# Top.net
KiCad netlist of a schematic drawn in Altium Designer
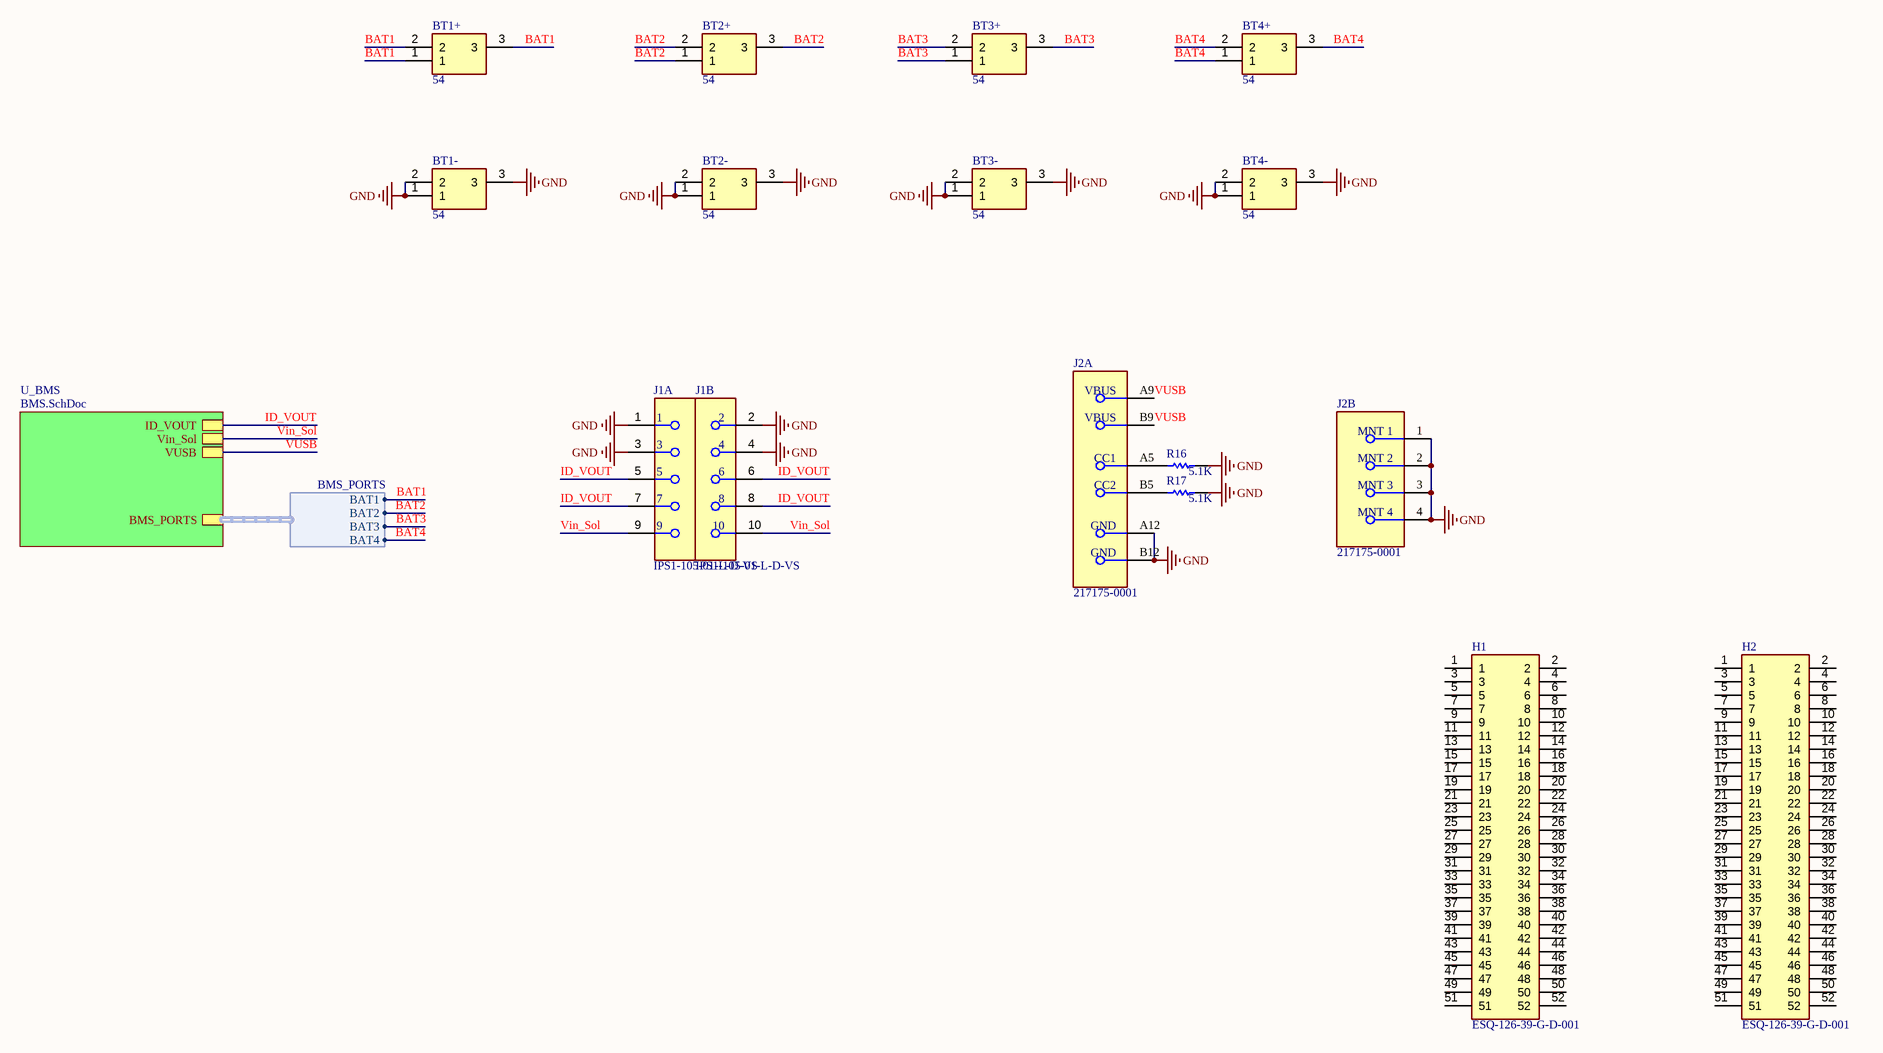
[diagram p0: Top.SchDoc]

(export (version "E")
  (design (tool "Eeschema 10.0.6"))
  (components
    (comp (ref "BT1+")
      (value "54")
      (footprint "54")
      (description "Battery")
      (fields (field (name "MOUSER PART NUMBER") "534-54"))
      (libsource (lib "Hitesh Bhoyar") (part "54"))
    )
    (comp (ref "BT1-")
      (value "54")
      (footprint "54")
      (description "Battery")
      (fields (field (name "MOUSER PART NUMBER") "534-54"))
      (libsource (lib "Hitesh Bhoyar") (part "54"))
    )
    (comp (ref "BT2+")
      (value "54")
      (footprint "54")
      (description "Battery")
      (fields (field (name "MOUSER PART NUMBER") "534-54"))
      (libsource (lib "Hitesh Bhoyar") (part "54"))
    )
    (comp (ref "BT2-")
      (value "54")
      (footprint "54")
      (description "Battery")
      (fields (field (name "MOUSER PART NUMBER") "534-54"))
      (libsource (lib "Hitesh Bhoyar") (part "54"))
    )
    (comp (ref "BT3+")
      (value "54")
      (footprint "54")
      (description "Battery")
      (fields (field (name "MOUSER PART NUMBER") "534-54"))
      (libsource (lib "Hitesh Bhoyar") (part "54"))
    )
    (comp (ref "BT3-")
      (value "54")
      (footprint "54")
      (description "Battery")
      (fields (field (name "MOUSER PART NUMBER") "534-54"))
      (libsource (lib "Hitesh Bhoyar") (part "54"))
    )
    (comp (ref "BT4+")
      (value "54")
      (footprint "54")
      (description "Battery")
      (fields (field (name "MOUSER PART NUMBER") "534-54"))
      (libsource (lib "Hitesh Bhoyar") (part "54"))
    )
    (comp (ref "BT4-")
      (value "54")
      (footprint "54")
      (description "Battery")
      (fields (field (name "MOUSER PART NUMBER") "534-54"))
      (libsource (lib "Hitesh Bhoyar") (part "54"))
    )
    (comp (ref "H1")
      (value "ESQ-126-39-G-D-001")
      (footprint "RHDR52W64P254_2X26_6654X495X1135P")
      (description "PC / 104 Connectors Elevated Socket Strip")
      (fields (field (name "MOUSER PART NUMBER") "200-ESQ12639GD001"))
      (libsource (lib "Hitesh Bhoyar") (part "ESQ-126-39-G-D-001"))
    )
    (comp (ref "H2")
      (value "ESQ-126-39-G-D-001")
      (footprint "RHDR52W64P254_2X26_6654X495X1135P")
      (description "PC / 104 Connectors Elevated Socket Strip")
      (fields (field (name "MOUSER PART NUMBER") "200-ESQ12639GD001"))
      (libsource (lib "Hitesh Bhoyar") (part "ESQ-126-39-G-D-001"))
    )
    (comp (ref "J1")
      (value "IPS1-105-01-L-D-VS")
      (footprint "FP-IPS1-105-01-L-D-VS-MFG")
      (description "CONN RCPT 10POS 0.1 GOLD SMD")
      (fields
        (field (name "MANUFACTURER") "Samtec")
        (field (name "OCTOPART") "https://octopart.com/ips1-105-01-l-d-vs-samtec-19544880")
      )
      (libsource (lib "Altium Content Vault") (part "393b6539e713c610e9ddbd64c51154e"))
    )
    (comp (ref "J2")
      (value "217175-0001")
      (footprint "FP-217175-0001-MFG")
      (description "CONN RCP USB2.0 C 6+18P SMD RA")
      (libsource (lib "Altium Content Vault") (part "6a66c69350f09309f94811689c98437"))
    )
    (comp (ref "R16")
      (value "5.1K")
      (footprint "RESC1608X55X30LL15T15")
      (fields (field (name "PART NUMBER") "ERJ-3GEYJ512V") (field (name "MANUFACTURER") "Panasonic"))
      (libsource (lib "Altium Content Vault") (part "RES"))
    )
    (comp (ref "R17")
      (value "5.1K")
      (footprint "RESC1608X55X30LL15T15")
      (fields (field (name "PART NUMBER") "ERJ-3GEYJ512V") (field (name "MANUFACTURER") "Panasonic"))
      (libsource (lib "Altium Content Vault") (part "RES"))
    )
  )
  (nets
    (net (code "2") (name "/BAT1") (class "Default")
      (node (ref "BT1+") (pin "1") (pinfunction "1_1") (pintype "passive"))
      (node (ref "BT1+") (pin "2") (pinfunction "2_2") (pintype "passive"))
      (node (ref "BT1+") (pin "3") (pinfunction "3_3") (pintype "passive"))
    )
    (net (code "3") (name "/BAT2") (class "Default")
      (node (ref "BT2+") (pin "1") (pinfunction "1_1") (pintype "passive"))
      (node (ref "BT2+") (pin "2") (pinfunction "2_2") (pintype "passive"))
      (node (ref "BT2+") (pin "3") (pinfunction "3_3") (pintype "passive"))
    )
    (net (code "4") (name "/BAT3") (class "Default")
      (node (ref "BT3+") (pin "1") (pinfunction "1_1") (pintype "passive"))
      (node (ref "BT3+") (pin "2") (pinfunction "2_2") (pintype "passive"))
      (node (ref "BT3+") (pin "3") (pinfunction "3_3") (pintype "passive"))
    )
    (net (code "5") (name "/BAT4") (class "Default")
      (node (ref "BT4+") (pin "1") (pinfunction "1_1") (pintype "passive"))
      (node (ref "BT4+") (pin "2") (pinfunction "2_2") (pintype "passive"))
      (node (ref "BT4+") (pin "3") (pinfunction "3_3") (pintype "passive"))
    )
    (net (code "6") (name "/ID_VOUT") (class "Default")
      (node (ref "J1") (pin "5") (pinfunction "5_5") (pintype "passive"))
      (node (ref "J1") (pin "6") (pinfunction "6_6") (pintype "passive"))
      (node (ref "J1") (pin "7") (pinfunction "7_7") (pintype "passive"))
      (node (ref "J1") (pin "8") (pinfunction "8_8") (pintype "passive"))
    )
    (net (code "7") (name "/VUSB") (class "Default")
      (node (ref "J2") (pin "A9") (pinfunction "VBUS_A9") (pintype "power_in"))
      (node (ref "J2") (pin "B9") (pinfunction "VBUS_B9") (pintype "power_in"))
    )
    (net (code "8") (name "/Vin_Sol") (class "Default")
      (node (ref "J1") (pin "10") (pinfunction "10_10") (pintype "passive"))
      (node (ref "J1") (pin "9") (pinfunction "9_9") (pintype "passive"))
    )
    (net (code "10") (name "GND") (class "Default")
      (node (ref "BT1-") (pin "1") (pinfunction "1_1") (pintype "passive"))
      (node (ref "BT1-") (pin "2") (pinfunction "2_2") (pintype "passive"))
      (node (ref "BT1-") (pin "3") (pinfunction "3_3") (pintype "passive"))
      (node (ref "BT2-") (pin "1") (pinfunction "1_1") (pintype "passive"))
      (node (ref "BT2-") (pin "2") (pinfunction "2_2") (pintype "passive"))
      (node (ref "BT2-") (pin "3") (pinfunction "3_3") (pintype "passive"))
      (node (ref "BT3-") (pin "1") (pinfunction "1_1") (pintype "passive"))
      (node (ref "BT3-") (pin "2") (pinfunction "2_2") (pintype "passive"))
      (node (ref "BT3-") (pin "3") (pinfunction "3_3") (pintype "passive"))
      (node (ref "BT4-") (pin "1") (pinfunction "1_1") (pintype "passive"))
      (node (ref "BT4-") (pin "2") (pinfunction "2_2") (pintype "passive"))
      (node (ref "BT4-") (pin "3") (pinfunction "3_3") (pintype "passive"))
      (node (ref "J1") (pin "1") (pinfunction "1_1") (pintype "passive"))
      (node (ref "J1") (pin "2") (pinfunction "2_2") (pintype "passive"))
      (node (ref "J1") (pin "3") (pinfunction "3_3") (pintype "passive"))
      (node (ref "J1") (pin "4") (pinfunction "4_4") (pintype "passive"))
      (node (ref "J2") (pin "1") (pinfunction "MNT_1_1") (pintype "passive"))
      (node (ref "J2") (pin "2") (pinfunction "MNT_2_2") (pintype "passive"))
      (node (ref "J2") (pin "3") (pinfunction "MNT_3_3") (pintype "passive"))
      (node (ref "J2") (pin "4") (pinfunction "MNT_4_4") (pintype "passive"))
      (node (ref "J2") (pin "A12") (pinfunction "GND_A12") (pintype "power_in"))
      (node (ref "J2") (pin "B12") (pinfunction "GND_B12") (pintype "power_in"))
      (node (ref "R16") (pin "2") (pinfunction "2_2") (pintype "passive"))
      (node (ref "R17") (pin "2") (pinfunction "2_2") (pintype "passive"))
    )
    (net (code "11") (name "Net-(J2A-CC1)") (class "Default")
      (node (ref "J2") (pin "A5") (pinfunction "CC1_A5") (pintype "passive"))
      (node (ref "R16") (pin "1") (pinfunction "1_1") (pintype "passive"))
    )
    (net (code "12") (name "Net-(J2A-CC2)") (class "Default")
      (node (ref "J2") (pin "B5") (pinfunction "CC2_B5") (pintype "passive"))
      (node (ref "R17") (pin "1") (pinfunction "1_1") (pintype "passive"))
    )
    (net (code "13") (name "unconnected-(H1-Pad1)") (class "Default")
      (node (ref "H1") (pin "1") (pinfunction "1_1") (pintype "passive"))
    )
    (net (code "14") (name "unconnected-(H1-Pad2)") (class "Default")
      (node (ref "H1") (pin "2") (pinfunction "2_2") (pintype "passive"))
    )
    (net (code "15") (name "unconnected-(H1-Pad3)") (class "Default")
      (node (ref "H1") (pin "3") (pinfunction "3_3") (pintype "passive"))
    )
    (net (code "16") (name "unconnected-(H1-Pad4)") (class "Default")
      (node (ref "H1") (pin "4") (pinfunction "4_4") (pintype "passive"))
    )
    (net (code "17") (name "unconnected-(H1-Pad5)") (class "Default")
      (node (ref "H1") (pin "5") (pinfunction "5_5") (pintype "passive"))
    )
    (net (code "18") (name "unconnected-(H1-Pad6)") (class "Default")
      (node (ref "H1") (pin "6") (pinfunction "6_6") (pintype "passive"))
    )
    (net (code "19") (name "unconnected-(H1-Pad7)") (class "Default")
      (node (ref "H1") (pin "7") (pinfunction "7_7") (pintype "passive"))
    )
    (net (code "20") (name "unconnected-(H1-Pad8)") (class "Default")
      (node (ref "H1") (pin "8") (pinfunction "8_8") (pintype "passive"))
    )
    (net (code "21") (name "unconnected-(H1-Pad9)") (class "Default")
      (node (ref "H1") (pin "9") (pinfunction "9_9") (pintype "passive"))
    )
    (net (code "22") (name "unconnected-(H1-Pad10)") (class "Default")
      (node (ref "H1") (pin "10") (pinfunction "10_10") (pintype "passive"))
    )
    (net (code "23") (name "unconnected-(H1-Pad11)") (class "Default")
      (node (ref "H1") (pin "11") (pinfunction "11_11") (pintype "passive"))
    )
    (net (code "24") (name "unconnected-(H1-Pad12)") (class "Default")
      (node (ref "H1") (pin "12") (pinfunction "12_12") (pintype "passive"))
    )
    (net (code "25") (name "unconnected-(H1-Pad13)") (class "Default")
      (node (ref "H1") (pin "13") (pinfunction "13_13") (pintype "passive"))
    )
    (net (code "26") (name "unconnected-(H1-Pad14)") (class "Default")
      (node (ref "H1") (pin "14") (pinfunction "14_14") (pintype "passive"))
    )
    (net (code "27") (name "unconnected-(H1-Pad15)") (class "Default")
      (node (ref "H1") (pin "15") (pinfunction "15_15") (pintype "passive"))
    )
    (net (code "28") (name "unconnected-(H1-Pad16)") (class "Default")
      (node (ref "H1") (pin "16") (pinfunction "16_16") (pintype "passive"))
    )
    (net (code "29") (name "unconnected-(H1-Pad17)") (class "Default")
      (node (ref "H1") (pin "17") (pinfunction "17_17") (pintype "passive"))
    )
    (net (code "30") (name "unconnected-(H1-Pad18)") (class "Default")
      (node (ref "H1") (pin "18") (pinfunction "18_18") (pintype "passive"))
    )
    (net (code "31") (name "unconnected-(H1-Pad19)") (class "Default")
      (node (ref "H1") (pin "19") (pinfunction "19_19") (pintype "passive"))
    )
    (net (code "32") (name "unconnected-(H1-Pad20)") (class "Default")
      (node (ref "H1") (pin "20") (pinfunction "20_20") (pintype "passive"))
    )
    (net (code "33") (name "unconnected-(H1-Pad21)") (class "Default")
      (node (ref "H1") (pin "21") (pinfunction "21_21") (pintype "passive"))
    )
    (net (code "34") (name "unconnected-(H1-Pad22)") (class "Default")
      (node (ref "H1") (pin "22") (pinfunction "22_22") (pintype "passive"))
    )
    (net (code "35") (name "unconnected-(H1-Pad23)") (class "Default")
      (node (ref "H1") (pin "23") (pinfunction "23_23") (pintype "passive"))
    )
    (net (code "36") (name "unconnected-(H1-Pad24)") (class "Default")
      (node (ref "H1") (pin "24") (pinfunction "24_24") (pintype "passive"))
    )
    (net (code "37") (name "unconnected-(H1-Pad25)") (class "Default")
      (node (ref "H1") (pin "25") (pinfunction "25_25") (pintype "passive"))
    )
    (net (code "38") (name "unconnected-(H1-Pad26)") (class "Default")
      (node (ref "H1") (pin "26") (pinfunction "26_26") (pintype "passive"))
    )
    (net (code "39") (name "unconnected-(H1-Pad27)") (class "Default")
      (node (ref "H1") (pin "27") (pinfunction "27_27") (pintype "passive"))
    )
    (net (code "40") (name "unconnected-(H1-Pad28)") (class "Default")
      (node (ref "H1") (pin "28") (pinfunction "28_28") (pintype "passive"))
    )
    (net (code "41") (name "unconnected-(H1-Pad29)") (class "Default")
      (node (ref "H1") (pin "29") (pinfunction "29_29") (pintype "passive"))
    )
    (net (code "42") (name "unconnected-(H1-Pad30)") (class "Default")
      (node (ref "H1") (pin "30") (pinfunction "30_30") (pintype "passive"))
    )
    (net (code "43") (name "unconnected-(H1-Pad31)") (class "Default")
      (node (ref "H1") (pin "31") (pinfunction "31_31") (pintype "passive"))
    )
    (net (code "44") (name "unconnected-(H1-Pad32)") (class "Default")
      (node (ref "H1") (pin "32") (pinfunction "32_32") (pintype "passive"))
    )
    (net (code "45") (name "unconnected-(H1-Pad33)") (class "Default")
      (node (ref "H1") (pin "33") (pinfunction "33_33") (pintype "passive"))
    )
    (net (code "46") (name "unconnected-(H1-Pad34)") (class "Default")
      (node (ref "H1") (pin "34") (pinfunction "34_34") (pintype "passive"))
    )
    (net (code "47") (name "unconnected-(H1-Pad35)") (class "Default")
      (node (ref "H1") (pin "35") (pinfunction "35_35") (pintype "passive"))
    )
    (net (code "48") (name "unconnected-(H1-Pad36)") (class "Default")
      (node (ref "H1") (pin "36") (pinfunction "36_36") (pintype "passive"))
    )
    (net (code "49") (name "unconnected-(H1-Pad37)") (class "Default")
      (node (ref "H1") (pin "37") (pinfunction "37_37") (pintype "passive"))
    )
    (net (code "50") (name "unconnected-(H1-Pad38)") (class "Default")
      (node (ref "H1") (pin "38") (pinfunction "38_38") (pintype "passive"))
    )
    (net (code "51") (name "unconnected-(H1-Pad39)") (class "Default")
      (node (ref "H1") (pin "39") (pinfunction "39_39") (pintype "passive"))
    )
    (net (code "52") (name "unconnected-(H1-Pad40)") (class "Default")
      (node (ref "H1") (pin "40") (pinfunction "40_40") (pintype "passive"))
    )
    (net (code "53") (name "unconnected-(H1-Pad41)") (class "Default")
      (node (ref "H1") (pin "41") (pinfunction "41_41") (pintype "passive"))
    )
    (net (code "54") (name "unconnected-(H1-Pad42)") (class "Default")
      (node (ref "H1") (pin "42") (pinfunction "42_42") (pintype "passive"))
    )
    (net (code "55") (name "unconnected-(H1-Pad43)") (class "Default")
      (node (ref "H1") (pin "43") (pinfunction "43_43") (pintype "passive"))
    )
    (net (code "56") (name "unconnected-(H1-Pad44)") (class "Default")
      (node (ref "H1") (pin "44") (pinfunction "44_44") (pintype "passive"))
    )
    (net (code "57") (name "unconnected-(H1-Pad45)") (class "Default")
      (node (ref "H1") (pin "45") (pinfunction "45_45") (pintype "passive"))
    )
    (net (code "58") (name "unconnected-(H1-Pad46)") (class "Default")
      (node (ref "H1") (pin "46") (pinfunction "46_46") (pintype "passive"))
    )
    (net (code "59") (name "unconnected-(H1-Pad47)") (class "Default")
      (node (ref "H1") (pin "47") (pinfunction "47_47") (pintype "passive"))
    )
    (net (code "60") (name "unconnected-(H1-Pad48)") (class "Default")
      (node (ref "H1") (pin "48") (pinfunction "48_48") (pintype "passive"))
    )
    (net (code "61") (name "unconnected-(H1-Pad49)") (class "Default")
      (node (ref "H1") (pin "49") (pinfunction "49_49") (pintype "passive"))
    )
    (net (code "62") (name "unconnected-(H1-Pad50)") (class "Default")
      (node (ref "H1") (pin "50") (pinfunction "50_50") (pintype "passive"))
    )
    (net (code "63") (name "unconnected-(H1-Pad51)") (class "Default")
      (node (ref "H1") (pin "51") (pinfunction "51_51") (pintype "passive"))
    )
    (net (code "64") (name "unconnected-(H1-Pad52)") (class "Default")
      (node (ref "H1") (pin "52") (pinfunction "52_52") (pintype "passive"))
    )
    (net (code "65") (name "unconnected-(H2-Pad1)") (class "Default")
      (node (ref "H2") (pin "1") (pinfunction "1_1") (pintype "passive"))
    )
    (net (code "66") (name "unconnected-(H2-Pad2)") (class "Default")
      (node (ref "H2") (pin "2") (pinfunction "2_2") (pintype "passive"))
    )
    (net (code "67") (name "unconnected-(H2-Pad3)") (class "Default")
      (node (ref "H2") (pin "3") (pinfunction "3_3") (pintype "passive"))
    )
    (net (code "68") (name "unconnected-(H2-Pad4)") (class "Default")
      (node (ref "H2") (pin "4") (pinfunction "4_4") (pintype "passive"))
    )
    (net (code "69") (name "unconnected-(H2-Pad5)") (class "Default")
      (node (ref "H2") (pin "5") (pinfunction "5_5") (pintype "passive"))
    )
    (net (code "70") (name "unconnected-(H2-Pad6)") (class "Default")
      (node (ref "H2") (pin "6") (pinfunction "6_6") (pintype "passive"))
    )
    (net (code "71") (name "unconnected-(H2-Pad7)") (class "Default")
      (node (ref "H2") (pin "7") (pinfunction "7_7") (pintype "passive"))
    )
    (net (code "72") (name "unconnected-(H2-Pad8)") (class "Default")
      (node (ref "H2") (pin "8") (pinfunction "8_8") (pintype "passive"))
    )
    (net (code "73") (name "unconnected-(H2-Pad9)") (class "Default")
      (node (ref "H2") (pin "9") (pinfunction "9_9") (pintype "passive"))
    )
    (net (code "74") (name "unconnected-(H2-Pad10)") (class "Default")
      (node (ref "H2") (pin "10") (pinfunction "10_10") (pintype "passive"))
    )
    (net (code "75") (name "unconnected-(H2-Pad11)") (class "Default")
      (node (ref "H2") (pin "11") (pinfunction "11_11") (pintype "passive"))
    )
    (net (code "76") (name "unconnected-(H2-Pad12)") (class "Default")
      (node (ref "H2") (pin "12") (pinfunction "12_12") (pintype "passive"))
    )
    (net (code "77") (name "unconnected-(H2-Pad13)") (class "Default")
      (node (ref "H2") (pin "13") (pinfunction "13_13") (pintype "passive"))
    )
    (net (code "78") (name "unconnected-(H2-Pad14)") (class "Default")
      (node (ref "H2") (pin "14") (pinfunction "14_14") (pintype "passive"))
    )
    (net (code "79") (name "unconnected-(H2-Pad15)") (class "Default")
      (node (ref "H2") (pin "15") (pinfunction "15_15") (pintype "passive"))
    )
    (net (code "80") (name "unconnected-(H2-Pad16)") (class "Default")
      (node (ref "H2") (pin "16") (pinfunction "16_16") (pintype "passive"))
    )
    (net (code "81") (name "unconnected-(H2-Pad17)") (class "Default")
      (node (ref "H2") (pin "17") (pinfunction "17_17") (pintype "passive"))
    )
    (net (code "82") (name "unconnected-(H2-Pad18)") (class "Default")
      (node (ref "H2") (pin "18") (pinfunction "18_18") (pintype "passive"))
    )
    (net (code "83") (name "unconnected-(H2-Pad19)") (class "Default")
      (node (ref "H2") (pin "19") (pinfunction "19_19") (pintype "passive"))
    )
    (net (code "84") (name "unconnected-(H2-Pad20)") (class "Default")
      (node (ref "H2") (pin "20") (pinfunction "20_20") (pintype "passive"))
    )
    (net (code "85") (name "unconnected-(H2-Pad21)") (class "Default")
      (node (ref "H2") (pin "21") (pinfunction "21_21") (pintype "passive"))
    )
    (net (code "86") (name "unconnected-(H2-Pad22)") (class "Default")
      (node (ref "H2") (pin "22") (pinfunction "22_22") (pintype "passive"))
    )
    (net (code "87") (name "unconnected-(H2-Pad23)") (class "Default")
      (node (ref "H2") (pin "23") (pinfunction "23_23") (pintype "passive"))
    )
    (net (code "88") (name "unconnected-(H2-Pad24)") (class "Default")
      (node (ref "H2") (pin "24") (pinfunction "24_24") (pintype "passive"))
    )
    (net (code "89") (name "unconnected-(H2-Pad25)") (class "Default")
      (node (ref "H2") (pin "25") (pinfunction "25_25") (pintype "passive"))
    )
    (net (code "90") (name "unconnected-(H2-Pad26)") (class "Default")
      (node (ref "H2") (pin "26") (pinfunction "26_26") (pintype "passive"))
    )
    (net (code "91") (name "unconnected-(H2-Pad27)") (class "Default")
      (node (ref "H2") (pin "27") (pinfunction "27_27") (pintype "passive"))
    )
    (net (code "92") (name "unconnected-(H2-Pad28)") (class "Default")
      (node (ref "H2") (pin "28") (pinfunction "28_28") (pintype "passive"))
    )
    (net (code "93") (name "unconnected-(H2-Pad29)") (class "Default")
      (node (ref "H2") (pin "29") (pinfunction "29_29") (pintype "passive"))
    )
    (net (code "94") (name "unconnected-(H2-Pad30)") (class "Default")
      (node (ref "H2") (pin "30") (pinfunction "30_30") (pintype "passive"))
    )
    (net (code "95") (name "unconnected-(H2-Pad31)") (class "Default")
      (node (ref "H2") (pin "31") (pinfunction "31_31") (pintype "passive"))
    )
    (net (code "96") (name "unconnected-(H2-Pad32)") (class "Default")
      (node (ref "H2") (pin "32") (pinfunction "32_32") (pintype "passive"))
    )
    (net (code "97") (name "unconnected-(H2-Pad33)") (class "Default")
      (node (ref "H2") (pin "33") (pinfunction "33_33") (pintype "passive"))
    )
    (net (code "98") (name "unconnected-(H2-Pad34)") (class "Default")
      (node (ref "H2") (pin "34") (pinfunction "34_34") (pintype "passive"))
    )
    (net (code "99") (name "unconnected-(H2-Pad35)") (class "Default")
      (node (ref "H2") (pin "35") (pinfunction "35_35") (pintype "passive"))
    )
    (net (code "100") (name "unconnected-(H2-Pad36)") (class "Default")
      (node (ref "H2") (pin "36") (pinfunction "36_36") (pintype "passive"))
    )
    (net (code "101") (name "unconnected-(H2-Pad37)") (class "Default")
      (node (ref "H2") (pin "37") (pinfunction "37_37") (pintype "passive"))
    )
    (net (code "102") (name "unconnected-(H2-Pad38)") (class "Default")
      (node (ref "H2") (pin "38") (pinfunction "38_38") (pintype "passive"))
    )
    (net (code "103") (name "unconnected-(H2-Pad39)") (class "Default")
      (node (ref "H2") (pin "39") (pinfunction "39_39") (pintype "passive"))
    )
    (net (code "104") (name "unconnected-(H2-Pad40)") (class "Default")
      (node (ref "H2") (pin "40") (pinfunction "40_40") (pintype "passive"))
    )
    (net (code "105") (name "unconnected-(H2-Pad41)") (class "Default")
      (node (ref "H2") (pin "41") (pinfunction "41_41") (pintype "passive"))
    )
    (net (code "106") (name "unconnected-(H2-Pad42)") (class "Default")
      (node (ref "H2") (pin "42") (pinfunction "42_42") (pintype "passive"))
    )
    (net (code "107") (name "unconnected-(H2-Pad43)") (class "Default")
      (node (ref "H2") (pin "43") (pinfunction "43_43") (pintype "passive"))
    )
    (net (code "108") (name "unconnected-(H2-Pad44)") (class "Default")
      (node (ref "H2") (pin "44") (pinfunction "44_44") (pintype "passive"))
    )
    (net (code "109") (name "unconnected-(H2-Pad45)") (class "Default")
      (node (ref "H2") (pin "45") (pinfunction "45_45") (pintype "passive"))
    )
    (net (code "110") (name "unconnected-(H2-Pad46)") (class "Default")
      (node (ref "H2") (pin "46") (pinfunction "46_46") (pintype "passive"))
    )
    (net (code "111") (name "unconnected-(H2-Pad47)") (class "Default")
      (node (ref "H2") (pin "47") (pinfunction "47_47") (pintype "passive"))
    )
    (net (code "112") (name "unconnected-(H2-Pad48)") (class "Default")
      (node (ref "H2") (pin "48") (pinfunction "48_48") (pintype "passive"))
    )
    (net (code "113") (name "unconnected-(H2-Pad49)") (class "Default")
      (node (ref "H2") (pin "49") (pinfunction "49_49") (pintype "passive"))
    )
    (net (code "114") (name "unconnected-(H2-Pad50)") (class "Default")
      (node (ref "H2") (pin "50") (pinfunction "50_50") (pintype "passive"))
    )
    (net (code "115") (name "unconnected-(H2-Pad51)") (class "Default")
      (node (ref "H2") (pin "51") (pinfunction "51_51") (pintype "passive"))
    )
    (net (code "116") (name "unconnected-(H2-Pad52)") (class "Default")
      (node (ref "H2") (pin "52") (pinfunction "52_52") (pintype "passive"))
    )
  )
)
